# VGA_breakout.net
KiCad netlist of a schematic drawn in Altium Designer
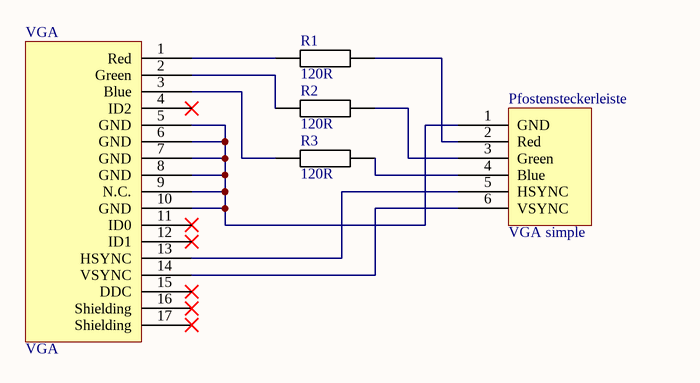
[diagram p0: VGA breakout.SchDoc]

(export (version "E")
  (design (tool "Eeschema 10.0.6"))
  (components
    (comp (ref "Pfostensteckerleiste")
      (value "VGA simple")
      (footprint "Header 1x6")
      (libsource (lib "Connectors") (part "VGA simple"))
    )
    (comp (ref "R1")
      (value "120R")
      (footprint "R 0805 / 2012")
      (libsource (lib "VGA breakout") (part "Resistor"))
    )
    (comp (ref "R2")
      (value "120R")
      (footprint "R 0805 / 2012")
      (libsource (lib "Standard") (part "Resistor"))
    )
    (comp (ref "R3")
      (value "120R")
      (footprint "R 0805 / 2012")
      (libsource (lib "Standard") (part "Resistor"))
    )
    (comp (ref "VGA") (value "VGA") (libsource (lib "Connectors") (part "VGA")))
  )
  (nets
    (net (code "1") (name "Net-(Pfostensteckerleiste-Blue)") (class "Default")
      (node (ref "Pfostensteckerleiste") (pin "4") (pinfunction "Blue_4") (pintype "passive"))
      (node (ref "R3") (pin "2") (pinfunction "2_2") (pintype "passive"))
    )
    (net (code "2") (name "Net-(Pfostensteckerleiste-GND)") (class "Default")
      (node (ref "Pfostensteckerleiste") (pin "1") (pinfunction "GND_1") (pintype "passive"))
      (node (ref "VGA") (pin "10") (pinfunction "GND_10") (pintype "passive"))
      (node (ref "VGA") (pin "5") (pinfunction "GND_5") (pintype "passive"))
      (node (ref "VGA") (pin "6") (pinfunction "GND_6") (pintype "passive"))
      (node (ref "VGA") (pin "7") (pinfunction "GND_7") (pintype "passive"))
      (node (ref "VGA") (pin "8") (pinfunction "GND_8") (pintype "passive"))
      (node (ref "VGA") (pin "9") (pinfunction "N.C._9") (pintype "passive"))
    )
    (net (code "3") (name "Net-(Pfostensteckerleiste-Green)") (class "Default")
      (node (ref "Pfostensteckerleiste") (pin "3") (pinfunction "Green_3") (pintype "passive"))
      (node (ref "R2") (pin "2") (pinfunction "2_2") (pintype "passive"))
    )
    (net (code "4") (name "Net-(Pfostensteckerleiste-HSYNC)") (class "Default")
      (node (ref "Pfostensteckerleiste") (pin "5") (pinfunction "HSYNC_5") (pintype "passive"))
      (node (ref "VGA") (pin "13") (pinfunction "HSYNC_13") (pintype "passive"))
    )
    (net (code "5") (name "Net-(Pfostensteckerleiste-Red)") (class "Default")
      (node (ref "Pfostensteckerleiste") (pin "2") (pinfunction "Red_2") (pintype "passive"))
      (node (ref "R1") (pin "2") (pinfunction "2_2") (pintype "passive"))
    )
    (net (code "6") (name "Net-(Pfostensteckerleiste-VSYNC)") (class "Default")
      (node (ref "Pfostensteckerleiste") (pin "6") (pinfunction "VSYNC_6") (pintype "passive"))
      (node (ref "VGA") (pin "14") (pinfunction "VSYNC_14") (pintype "passive"))
    )
    (net (code "7") (name "Net-(VGA-Blue)") (class "Default")
      (node (ref "R3") (pin "1") (pinfunction "1_1") (pintype "passive"))
      (node (ref "VGA") (pin "3") (pinfunction "Blue_3") (pintype "passive"))
    )
    (net (code "8") (name "Net-(VGA-Green)") (class "Default")
      (node (ref "R2") (pin "1") (pinfunction "1_1") (pintype "passive"))
      (node (ref "VGA") (pin "2") (pinfunction "Green_2") (pintype "passive"))
    )
    (net (code "9") (name "Net-(VGA-Red)") (class "Default")
      (node (ref "R1") (pin "1") (pinfunction "1_1") (pintype "passive"))
      (node (ref "VGA") (pin "1") (pinfunction "Red_1") (pintype "passive"))
    )
    (net (code "10") (name "unconnected-(VGA-DDC-Pad15)") (class "Default")
      (node (ref "VGA") (pin "15") (pinfunction "DDC_15") (pintype "passive+no_connect"))
    )
    (net (code "11") (name "unconnected-(VGA-ID0-Pad11)") (class "Default")
      (node (ref "VGA") (pin "11") (pinfunction "ID0_11") (pintype "passive+no_connect"))
    )
    (net (code "12") (name "unconnected-(VGA-ID1-Pad12)") (class "Default")
      (node (ref "VGA") (pin "12") (pinfunction "ID1_12") (pintype "passive+no_connect"))
    )
    (net (code "13") (name "unconnected-(VGA-ID2-Pad4)") (class "Default")
      (node (ref "VGA") (pin "4") (pinfunction "ID2_4") (pintype "passive+no_connect"))
    )
    (net (code "14") (name "unconnected-(VGA-Shielding-Pad16)") (class "Default")
      (node (ref "VGA") (pin "16") (pinfunction "Shielding_16") (pintype "passive+no_connect"))
    )
    (net (code "15") (name "unconnected-(VGA-Shielding-Pad17)") (class "Default")
      (node (ref "VGA") (pin "17") (pinfunction "Shielding_17") (pintype "passive+no_connect"))
    )
  )
)
